# obd25k80.net
KiCad netlist of a schematic drawn in EAGLE
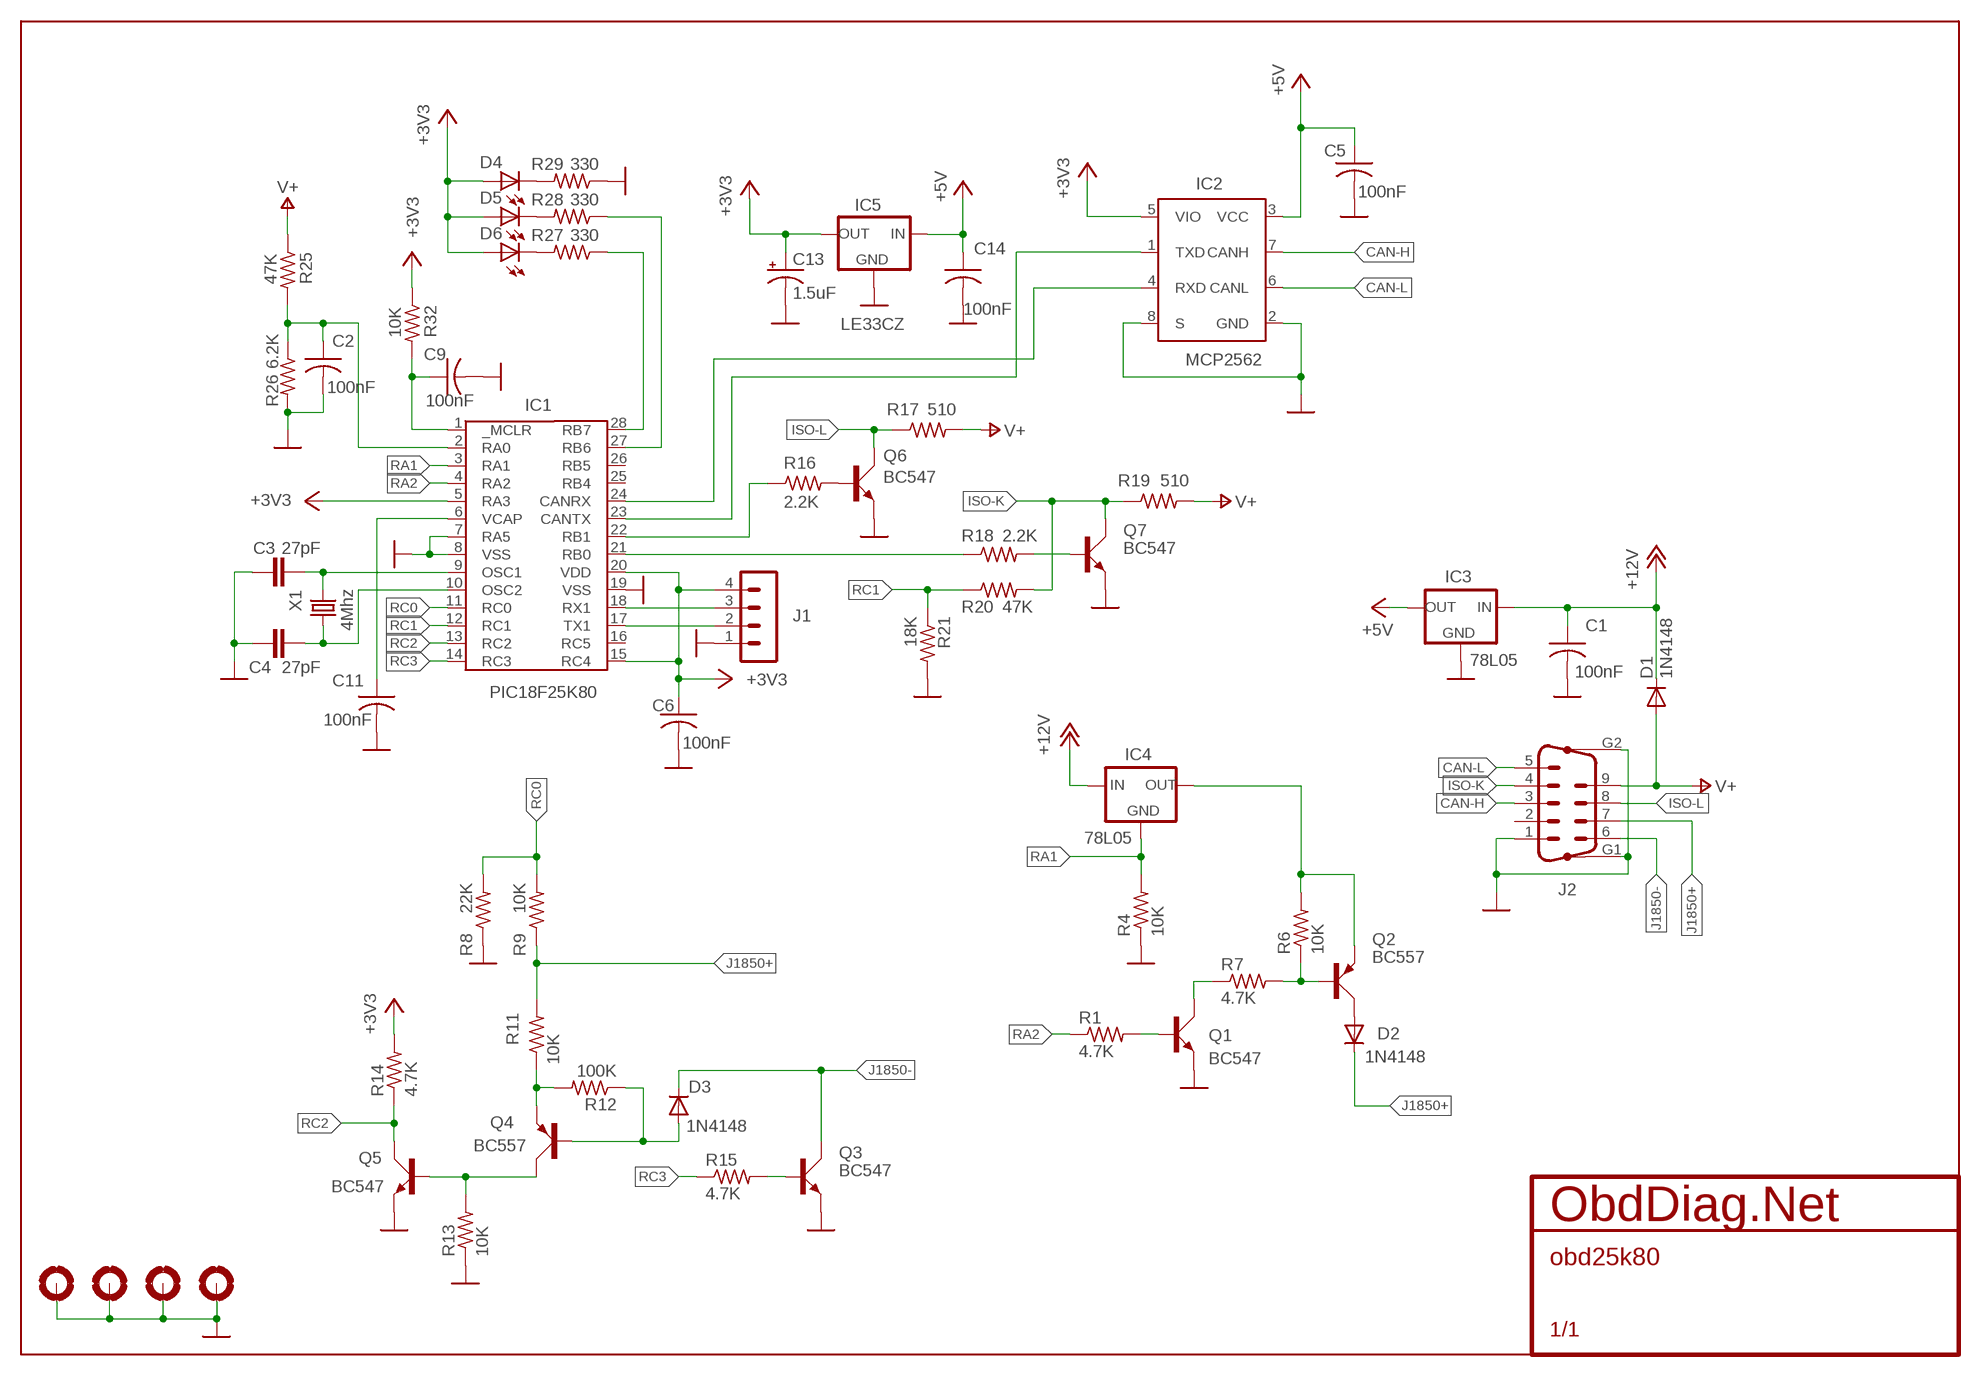
[diagram p0: schematic, sheet 1]

(export (version "E")
  (design (tool "Eeschema 10.0.6"))
  (components
    (comp (ref "C1")
      (value "100nF")
      (footprint "eagle-import:C050-025X075")
      (libsource (lib "eagle-import") (part "C-US050-025X075"))
    )
    (comp (ref "C2")
      (value "100nF")
      (footprint "eagle-import:C050-025X075")
      (libsource (lib "eagle-import") (part "C-US050-025X075"))
    )
    (comp (ref "C3")
      (value "27pF")
      (footprint "eagle-import:C2.5-2")
      (libsource (lib "eagle-import") (part "C2.5/2"))
    )
    (comp (ref "C4")
      (value "27pF")
      (footprint "eagle-import:C2.5-2")
      (libsource (lib "eagle-import") (part "C2.5/2"))
    )
    (comp (ref "C5")
      (value "100nF")
      (footprint "eagle-import:C050-025X075")
      (libsource (lib "eagle-import") (part "C-US050-025X075"))
    )
    (comp (ref "C6")
      (value "100nF")
      (footprint "eagle-import:C050-025X075")
      (libsource (lib "eagle-import") (part "C-US050-025X075"))
    )
    (comp (ref "C9")
      (value "100nF")
      (footprint "eagle-import:C050-025X075")
      (libsource (lib "eagle-import") (part "C-US050-025X075"))
    )
    (comp (ref "C11")
      (value "100nF")
      (footprint "eagle-import:C050-025X075")
      (libsource (lib "eagle-import") (part "C-US050-025X075"))
    )
    (comp (ref "C13")
      (value "1.5uF")
      (footprint "eagle-import:E2,5-5")
      (libsource (lib "eagle-import") (part "CPOL-USE2.5-5"))
    )
    (comp (ref "C14")
      (value "100nF")
      (footprint "eagle-import:C050-025X075")
      (libsource (lib "eagle-import") (part "C-US050-025X075"))
    )
    (comp (ref "D1")
      (value "1N4148")
      (footprint "eagle-import:D035-10M")
      (libsource (lib "eagle-import") (part "1N4148M"))
    )
    (comp (ref "D2")
      (value "1N4148")
      (footprint "eagle-import:D035-10M")
      (libsource (lib "eagle-import") (part "1N4148M"))
    )
    (comp (ref "D3")
      (value "1N4148")
      (footprint "eagle-import:D035-10M")
      (libsource (lib "eagle-import") (part "1N4148M"))
    )
    (comp (ref "D4")
      (value "LED5MM")
      (footprint "eagle-import:LED5MM")
      (libsource (lib "eagle-import") (part "LED5MM"))
    )
    (comp (ref "D5")
      (value "LED5MM")
      (footprint "eagle-import:LED5MM")
      (libsource (lib "eagle-import") (part "LED5MM"))
    )
    (comp (ref "D6")
      (value "LED5MM")
      (footprint "eagle-import:LED5MM")
      (libsource (lib "eagle-import") (part "LED5MM"))
    )
    (comp (ref "H1")
      (value "MOUNT-PAD-ROUND2.8")
      (footprint "eagle-import:2,8-PAD")
      (libsource (lib "eagle-import") (part "MOUNT-PAD-ROUND2.8"))
    )
    (comp (ref "H2")
      (value "MOUNT-PAD-ROUND2.8")
      (footprint "eagle-import:2,8-PAD")
      (libsource (lib "eagle-import") (part "MOUNT-PAD-ROUND2.8"))
    )
    (comp (ref "H3")
      (value "MOUNT-PAD-ROUND2.8")
      (footprint "eagle-import:2,8-PAD")
      (libsource (lib "eagle-import") (part "MOUNT-PAD-ROUND2.8"))
    )
    (comp (ref "H4")
      (value "MOUNT-PAD-ROUND2.8")
      (footprint "eagle-import:2,8-PAD")
      (libsource (lib "eagle-import") (part "MOUNT-PAD-ROUND2.8"))
    )
    (comp (ref "IC1")
      (value "PIC18F25K80")
      (footprint "eagle-import:DIL28")
      (libsource (lib "eagle-import") (part "PIC18F25K80"))
    )
    (comp (ref "IC2")
      (value "MCP2562")
      (footprint "eagle-import:DIL8")
      (libsource (lib "eagle-import") (part "MCP2562"))
    )
    (comp (ref "IC3")
      (value "78L05")
      (footprint "eagle-import:78LXX")
      (libsource (lib "eagle-import") (part "78LXX"))
    )
    (comp (ref "IC4")
      (value "78L05")
      (footprint "eagle-import:78LXX")
      (libsource (lib "eagle-import") (part "78LXX"))
    )
    (comp (ref "IC5")
      (value "LE33CZ")
      (footprint "eagle-import:78LXX")
      (libsource (lib "eagle-import") (part "78LXX"))
    )
    (comp (ref "J1")
      (value "MA04-1")
      (footprint "eagle-import:MA04-1")
      (libsource (lib "eagle-import") (part "MA04-1"))
    )
    (comp (ref "J2")
      (value "DB9-M")
      (footprint "eagle-import:M09HP")
      (libsource (lib "eagle-import") (part "M09HP"))
    )
    (comp (ref "Q1")
      (value "BC547")
      (footprint "eagle-import:SOT54A")
      (libsource (lib "eagle-import") (part "BC547"))
    )
    (comp (ref "Q2")
      (value "BC557")
      (footprint "eagle-import:SOT54A")
      (libsource (lib "eagle-import") (part "BC557"))
    )
    (comp (ref "Q3")
      (value "BC547")
      (footprint "eagle-import:SOT54A")
      (libsource (lib "eagle-import") (part "BC547"))
    )
    (comp (ref "Q4")
      (value "BC557")
      (footprint "eagle-import:SOT54A")
      (libsource (lib "eagle-import") (part "BC557"))
    )
    (comp (ref "Q5")
      (value "BC547")
      (footprint "eagle-import:SOT54A")
      (libsource (lib "eagle-import") (part "BC547"))
    )
    (comp (ref "Q6")
      (value "BC547")
      (footprint "eagle-import:SOT54A")
      (libsource (lib "eagle-import") (part "BC547"))
    )
    (comp (ref "Q7")
      (value "BC547")
      (footprint "eagle-import:SOT54A")
      (libsource (lib "eagle-import") (part "BC547"))
    )
    (comp (ref "R1")
      (value "4.7K")
      (footprint "eagle-import:0207_10")
      (libsource (lib "eagle-import") (part "R-US_0207/10"))
    )
    (comp (ref "R4")
      (value "10K")
      (footprint "eagle-import:0207_10")
      (libsource (lib "eagle-import") (part "R-US_0207/10"))
    )
    (comp (ref "R6")
      (value "10K")
      (footprint "eagle-import:0207_10")
      (libsource (lib "eagle-import") (part "R-US_0207/10"))
    )
    (comp (ref "R7")
      (value "4.7K")
      (footprint "eagle-import:0207_10")
      (libsource (lib "eagle-import") (part "R-US_0207/10"))
    )
    (comp (ref "R8")
      (value "22K")
      (footprint "eagle-import:0207_10")
      (libsource (lib "eagle-import") (part "R-US_0207/10"))
    )
    (comp (ref "R9")
      (value "10K")
      (footprint "eagle-import:0207_10")
      (libsource (lib "eagle-import") (part "R-US_0207/10"))
    )
    (comp (ref "R11")
      (value "10K")
      (footprint "eagle-import:0207_10")
      (libsource (lib "eagle-import") (part "R-US_0207/10"))
    )
    (comp (ref "R12")
      (value "100K")
      (footprint "eagle-import:0207_10")
      (libsource (lib "eagle-import") (part "R-US_0207/10"))
    )
    (comp (ref "R13")
      (value "10K")
      (footprint "eagle-import:0207_10")
      (libsource (lib "eagle-import") (part "R-US_0207/10"))
    )
    (comp (ref "R14")
      (value "4.7K")
      (footprint "eagle-import:0207_10")
      (libsource (lib "eagle-import") (part "R-US_0207/10"))
    )
    (comp (ref "R15")
      (value "4.7K")
      (footprint "eagle-import:0207_10")
      (libsource (lib "eagle-import") (part "R-US_0207/10"))
    )
    (comp (ref "R16")
      (value "2.2K")
      (footprint "eagle-import:0207_10")
      (libsource (lib "eagle-import") (part "R-US_0207/10"))
    )
    (comp (ref "R17")
      (value "510")
      (footprint "eagle-import:0207_10")
      (libsource (lib "eagle-import") (part "R-US_0207/10"))
    )
    (comp (ref "R18")
      (value "2.2K")
      (footprint "eagle-import:0207_10")
      (libsource (lib "eagle-import") (part "R-US_0207/10"))
    )
    (comp (ref "R19")
      (value "510")
      (footprint "eagle-import:0207_10")
      (libsource (lib "eagle-import") (part "R-US_0207/10"))
    )
    (comp (ref "R20")
      (value "47K")
      (footprint "eagle-import:0207_10")
      (libsource (lib "eagle-import") (part "R-US_0207/10"))
    )
    (comp (ref "R21")
      (value "18K")
      (footprint "eagle-import:0207_10")
      (libsource (lib "eagle-import") (part "R-US_0207/10"))
    )
    (comp (ref "R25")
      (value "47K")
      (footprint "eagle-import:0207_10")
      (libsource (lib "eagle-import") (part "R-US_0207/10"))
    )
    (comp (ref "R26")
      (value "6.2K")
      (footprint "eagle-import:0207_10")
      (libsource (lib "eagle-import") (part "R-US_0207/10"))
    )
    (comp (ref "R27")
      (value "330")
      (footprint "eagle-import:0207_10")
      (libsource (lib "eagle-import") (part "R-US_0207/10"))
    )
    (comp (ref "R28")
      (value "330")
      (footprint "eagle-import:0207_10")
      (libsource (lib "eagle-import") (part "R-US_0207/10"))
    )
    (comp (ref "R29")
      (value "330")
      (footprint "eagle-import:0207_10")
      (libsource (lib "eagle-import") (part "R-US_0207/10"))
    )
    (comp (ref "R32")
      (value "10K")
      (footprint "eagle-import:0207_10")
      (libsource (lib "eagle-import") (part "R-US_0207/10"))
    )
    (comp (ref "X1")
      (value "4Mhz")
      (footprint "eagle-import:HC49_S")
      (libsource (lib "eagle-import") (part "CRYTALHC49S"))
    )
  )
  (nets
    (net (code "1") (name "+3V3") (class "Default")
      (node (ref "C13") (pin "+") (pinfunction "+_+") (pintype "passive"))
      (node (ref "C6") (pin "1") (pinfunction "1_1") (pintype "passive"))
      (node (ref "D4") (pin "A") (pinfunction "A_A") (pintype "passive"))
      (node (ref "D5") (pin "A") (pinfunction "A_A") (pintype "passive"))
      (node (ref "D6") (pin "A") (pinfunction "A_A") (pintype "passive"))
      (node (ref "IC1") (pin "15") (pinfunction "RC4_15") (pintype "bidirectional"))
      (node (ref "IC1") (pin "20") (pinfunction "VDD_20") (pintype "power_in"))
      (node (ref "IC1") (pin "5") (pinfunction "RA3_5") (pintype "bidirectional"))
      (node (ref "IC2") (pin "5") (pinfunction "VIO_5") (pintype "power_in"))
      (node (ref "IC5") (pin "OUT") (pinfunction "OUT_OUT") (pintype "passive"))
      (node (ref "J1") (pin "4") (pinfunction "4_4") (pintype "passive"))
      (node (ref "R14") (pin "2") (pinfunction "2_2") (pintype "passive"))
      (node (ref "R32") (pin "1") (pinfunction "1_1") (pintype "passive"))
    )
    (net (code "2") (name "+5V") (class "Default")
      (node (ref "C14") (pin "1") (pinfunction "1_1") (pintype "passive"))
      (node (ref "C5") (pin "1") (pinfunction "1_1") (pintype "passive"))
      (node (ref "IC2") (pin "3") (pinfunction "VCC_3") (pintype "power_in"))
      (node (ref "IC3") (pin "OUT") (pinfunction "OUT_OUT") (pintype "passive"))
      (node (ref "IC5") (pin "IN") (pinfunction "IN_IN") (pintype "input"))
    )
    (net (code "3") (name "+12V") (class "Default")
      (node (ref "C1") (pin "1") (pinfunction "1_1") (pintype "passive"))
      (node (ref "D1") (pin "C") (pinfunction "C_C") (pintype "passive"))
      (node (ref "IC3") (pin "IN") (pinfunction "IN_IN") (pintype "input"))
      (node (ref "IC4") (pin "IN") (pinfunction "IN_IN") (pintype "input"))
    )
    (net (code "4") (name "CAN-H") (class "Default")
      (node (ref "IC2") (pin "7") (pinfunction "CANH_7") (pintype "bidirectional"))
      (node (ref "J2") (pin "3") (pinfunction "3_3") (pintype "passive"))
    )
    (net (code "5") (name "CAN-L") (class "Default")
      (node (ref "IC2") (pin "6") (pinfunction "CANL_6") (pintype "bidirectional"))
      (node (ref "J2") (pin "5") (pinfunction "5_5") (pintype "passive"))
    )
    (net (code "6") (name "GND") (class "Default")
      (node (ref "C1") (pin "2") (pinfunction "2_2") (pintype "passive"))
      (node (ref "C11") (pin "2") (pinfunction "2_2") (pintype "passive"))
      (node (ref "C13") (pin "-") (pinfunction "-_-") (pintype "passive"))
      (node (ref "C14") (pin "2") (pinfunction "2_2") (pintype "passive"))
      (node (ref "C2") (pin "2") (pinfunction "2_2") (pintype "passive"))
      (node (ref "C3") (pin "1") (pinfunction "1_1") (pintype "passive"))
      (node (ref "C4") (pin "2") (pinfunction "2_2") (pintype "passive"))
      (node (ref "C5") (pin "2") (pinfunction "2_2") (pintype "passive"))
      (node (ref "C6") (pin "2") (pinfunction "2_2") (pintype "passive"))
      (node (ref "C9") (pin "2") (pinfunction "2_2") (pintype "passive"))
      (node (ref "H1") (pin "B2,8") (pinfunction "MOUNT_B2,8") (pintype "passive"))
      (node (ref "H2") (pin "B2,8") (pinfunction "MOUNT_B2,8") (pintype "passive"))
      (node (ref "H3") (pin "B2,8") (pinfunction "MOUNT_B2,8") (pintype "passive"))
      (node (ref "H4") (pin "B2,8") (pinfunction "MOUNT_B2,8") (pintype "passive"))
      (node (ref "IC1") (pin "19") (pinfunction "VSS_19") (pintype "power_in"))
      (node (ref "IC1") (pin "7") (pinfunction "RA5_7") (pintype "bidirectional"))
      (node (ref "IC1") (pin "8") (pinfunction "VSS_8") (pintype "power_in"))
      (node (ref "IC2") (pin "2") (pinfunction "GND_2") (pintype "power_in"))
      (node (ref "IC2") (pin "8") (pinfunction "S_8") (pintype "input"))
      (node (ref "IC3") (pin "GND") (pinfunction "GND_GND") (pintype "input"))
      (node (ref "IC5") (pin "GND") (pinfunction "GND_GND") (pintype "input"))
      (node (ref "J1") (pin "1") (pinfunction "1_1") (pintype "passive"))
      (node (ref "J2") (pin "1") (pinfunction "1_1") (pintype "passive"))
      (node (ref "J2") (pin "G1") (pinfunction "G1_G1") (pintype "passive"))
      (node (ref "J2") (pin "G2") (pinfunction "G2_G2") (pintype "passive"))
      (node (ref "Q1") (pin "E") (pinfunction "E_E") (pintype "passive"))
      (node (ref "Q3") (pin "E") (pinfunction "E_E") (pintype "passive"))
      (node (ref "Q5") (pin "E") (pinfunction "E_E") (pintype "passive"))
      (node (ref "Q6") (pin "E") (pinfunction "E_E") (pintype "passive"))
      (node (ref "Q7") (pin "E") (pinfunction "E_E") (pintype "passive"))
      (node (ref "R13") (pin "1") (pinfunction "1_1") (pintype "passive"))
      (node (ref "R21") (pin "2") (pinfunction "2_2") (pintype "passive"))
      (node (ref "R26") (pin "2") (pinfunction "2_2") (pintype "passive"))
      (node (ref "R29") (pin "1") (pinfunction "1_1") (pintype "passive"))
      (node (ref "R4") (pin "1") (pinfunction "1_1") (pintype "passive"))
      (node (ref "R8") (pin "1") (pinfunction "1_1") (pintype "passive"))
    )
    (net (code "7") (name "ISO-K") (class "Default")
      (node (ref "J2") (pin "4") (pinfunction "4_4") (pintype "passive"))
      (node (ref "Q7") (pin "C") (pinfunction "C_C") (pintype "passive"))
      (node (ref "R19") (pin "1") (pinfunction "1_1") (pintype "passive"))
      (node (ref "R20") (pin "2") (pinfunction "2_2") (pintype "passive"))
    )
    (net (code "8") (name "ISO-L") (class "Default")
      (node (ref "J2") (pin "8") (pinfunction "8_8") (pintype "passive"))
      (node (ref "Q6") (pin "C") (pinfunction "C_C") (pintype "passive"))
      (node (ref "R17") (pin "1") (pinfunction "1_1") (pintype "passive"))
    )
    (net (code "9") (name "J1850+") (class "Default")
      (node (ref "D2") (pin "C") (pinfunction "C_C") (pintype "passive"))
      (node (ref "J2") (pin "7") (pinfunction "7_7") (pintype "passive"))
      (node (ref "R11") (pin "2") (pinfunction "2_2") (pintype "passive"))
      (node (ref "R9") (pin "1") (pinfunction "1_1") (pintype "passive"))
    )
    (net (code "10") (name "J1850-") (class "Default")
      (node (ref "D3") (pin "C") (pinfunction "C_C") (pintype "passive"))
      (node (ref "J2") (pin "6") (pinfunction "6_6") (pintype "passive"))
      (node (ref "Q3") (pin "C") (pinfunction "C_C") (pintype "passive"))
    )
    (net (code "11") (name "Net-(D2-PadA)") (class "Default")
      (node (ref "D2") (pin "A") (pinfunction "A_A") (pintype "passive"))
      (node (ref "Q2") (pin "C") (pinfunction "C_C") (pintype "passive"))
    )
    (net (code "12") (name "Net-(D3-PadA)") (class "Default")
      (node (ref "D3") (pin "A") (pinfunction "A_A") (pintype "passive"))
      (node (ref "Q4") (pin "B") (pinfunction "B_B") (pintype "passive"))
      (node (ref "R12") (pin "1") (pinfunction "1_1") (pintype "passive"))
    )
    (net (code "13") (name "Net-(D4-C)") (class "Default")
      (node (ref "D4") (pin "K") (pinfunction "C_K") (pintype "passive"))
      (node (ref "R29") (pin "2") (pinfunction "2_2") (pintype "passive"))
    )
    (net (code "14") (name "Net-(D5-C)") (class "Default")
      (node (ref "D5") (pin "K") (pinfunction "C_K") (pintype "passive"))
      (node (ref "R28") (pin "2") (pinfunction "2_2") (pintype "passive"))
    )
    (net (code "15") (name "Net-(D6-C)") (class "Default")
      (node (ref "D6") (pin "K") (pinfunction "C_K") (pintype "passive"))
      (node (ref "R27") (pin "2") (pinfunction "2_2") (pintype "passive"))
    )
    (net (code "16") (name "Net-(IC1-CANRX)") (class "Default")
      (node (ref "IC1") (pin "24") (pinfunction "CANRX_24") (pintype "bidirectional"))
      (node (ref "IC2") (pin "4") (pinfunction "RXD_4") (pintype "output"))
    )
    (net (code "17") (name "Net-(IC1-CANTX)") (class "Default")
      (node (ref "IC1") (pin "23") (pinfunction "CANTX_23") (pintype "bidirectional"))
      (node (ref "IC2") (pin "1") (pinfunction "TXD_1") (pintype "input"))
    )
    (net (code "18") (name "Net-(IC1-OSC1)") (class "Default")
      (node (ref "C3") (pin "2") (pinfunction "2_2") (pintype "passive"))
      (node (ref "IC1") (pin "9") (pinfunction "OSC1_9") (pintype "bidirectional"))
      (node (ref "X1") (pin "2") (pinfunction "2_2") (pintype "passive"))
    )
    (net (code "19") (name "Net-(IC1-OSC2)") (class "Default")
      (node (ref "C4") (pin "1") (pinfunction "1_1") (pintype "passive"))
      (node (ref "IC1") (pin "10") (pinfunction "OSC2_10") (pintype "bidirectional"))
      (node (ref "X1") (pin "1") (pinfunction "1_1") (pintype "passive"))
    )
    (net (code "20") (name "Net-(IC1-RA0)") (class "Default")
      (node (ref "C2") (pin "1") (pinfunction "1_1") (pintype "passive"))
      (node (ref "IC1") (pin "2") (pinfunction "RA0_2") (pintype "bidirectional"))
      (node (ref "R25") (pin "2") (pinfunction "2_2") (pintype "passive"))
      (node (ref "R26") (pin "1") (pinfunction "1_1") (pintype "passive"))
    )
    (net (code "21") (name "Net-(IC1-RB0)") (class "Default")
      (node (ref "IC1") (pin "21") (pinfunction "RB0_21") (pintype "bidirectional"))
      (node (ref "R18") (pin "1") (pinfunction "1_1") (pintype "passive"))
    )
    (net (code "22") (name "Net-(IC1-RB1)") (class "Default")
      (node (ref "IC1") (pin "22") (pinfunction "RB1_22") (pintype "bidirectional"))
      (node (ref "R16") (pin "1") (pinfunction "1_1") (pintype "passive"))
    )
    (net (code "23") (name "Net-(IC1-RB6)") (class "Default")
      (node (ref "IC1") (pin "27") (pinfunction "RB6_27") (pintype "bidirectional"))
      (node (ref "R28") (pin "1") (pinfunction "1_1") (pintype "passive"))
    )
    (net (code "24") (name "Net-(IC1-RB7)") (class "Default")
      (node (ref "IC1") (pin "28") (pinfunction "RB7_28") (pintype "bidirectional"))
      (node (ref "R27") (pin "1") (pinfunction "1_1") (pintype "passive"))
    )
    (net (code "25") (name "Net-(IC1-RX1)") (class "Default")
      (node (ref "IC1") (pin "18") (pinfunction "RX1_18") (pintype "bidirectional"))
      (node (ref "J1") (pin "3") (pinfunction "3_3") (pintype "passive"))
    )
    (net (code "26") (name "Net-(IC1-TX1)") (class "Default")
      (node (ref "IC1") (pin "17") (pinfunction "TX1_17") (pintype "bidirectional"))
      (node (ref "J1") (pin "2") (pinfunction "2_2") (pintype "passive"))
    )
    (net (code "27") (name "Net-(IC1-VCAP)") (class "Default")
      (node (ref "C11") (pin "1") (pinfunction "1_1") (pintype "passive"))
      (node (ref "IC1") (pin "6") (pinfunction "VCAP_6") (pintype "passive"))
    )
    (net (code "28") (name "Net-(IC1-_MCLR)") (class "Default")
      (node (ref "C9") (pin "1") (pinfunction "1_1") (pintype "passive"))
      (node (ref "IC1") (pin "1") (pinfunction "_MCLR_1") (pintype "bidirectional"))
      (node (ref "R32") (pin "2") (pinfunction "2_2") (pintype "passive"))
    )
    (net (code "29") (name "Net-(IC4-PadOUT)") (class "Default")
      (node (ref "IC4") (pin "OUT") (pinfunction "OUT_OUT") (pintype "passive"))
      (node (ref "Q2") (pin "E") (pinfunction "E_E") (pintype "passive"))
      (node (ref "R6") (pin "2") (pinfunction "2_2") (pintype "passive"))
    )
    (net (code "30") (name "Net-(Q1-PadB)") (class "Default")
      (node (ref "Q1") (pin "B") (pinfunction "B_B") (pintype "passive"))
      (node (ref "R1") (pin "2") (pinfunction "2_2") (pintype "passive"))
    )
    (net (code "31") (name "Net-(Q1-PadC)") (class "Default")
      (node (ref "Q1") (pin "C") (pinfunction "C_C") (pintype "passive"))
      (node (ref "R7") (pin "1") (pinfunction "1_1") (pintype "passive"))
    )
    (net (code "32") (name "Net-(Q2-PadB)") (class "Default")
      (node (ref "Q2") (pin "B") (pinfunction "B_B") (pintype "passive"))
      (node (ref "R6") (pin "1") (pinfunction "1_1") (pintype "passive"))
      (node (ref "R7") (pin "2") (pinfunction "2_2") (pintype "passive"))
    )
    (net (code "33") (name "Net-(Q3-PadB)") (class "Default")
      (node (ref "Q3") (pin "B") (pinfunction "B_B") (pintype "passive"))
      (node (ref "R15") (pin "2") (pinfunction "2_2") (pintype "passive"))
    )
    (net (code "34") (name "Net-(Q4-PadC)") (class "Default")
      (node (ref "Q4") (pin "C") (pinfunction "C_C") (pintype "passive"))
      (node (ref "Q5") (pin "B") (pinfunction "B_B") (pintype "passive"))
      (node (ref "R13") (pin "2") (pinfunction "2_2") (pintype "passive"))
    )
    (net (code "35") (name "Net-(Q4-PadE)") (class "Default")
      (node (ref "Q4") (pin "E") (pinfunction "E_E") (pintype "passive"))
      (node (ref "R11") (pin "1") (pinfunction "1_1") (pintype "passive"))
      (node (ref "R12") (pin "2") (pinfunction "2_2") (pintype "passive"))
    )
    (net (code "36") (name "Net-(Q6-PadB)") (class "Default")
      (node (ref "Q6") (pin "B") (pinfunction "B_B") (pintype "passive"))
      (node (ref "R16") (pin "2") (pinfunction "2_2") (pintype "passive"))
    )
    (net (code "37") (name "Net-(Q7-PadB)") (class "Default")
      (node (ref "Q7") (pin "B") (pinfunction "B_B") (pintype "passive"))
      (node (ref "R18") (pin "2") (pinfunction "2_2") (pintype "passive"))
    )
    (net (code "38") (name "RA1") (class "Default")
      (node (ref "IC1") (pin "3") (pinfunction "RA1_3") (pintype "bidirectional"))
      (node (ref "IC4") (pin "GND") (pinfunction "GND_GND") (pintype "input"))
      (node (ref "R4") (pin "2") (pinfunction "2_2") (pintype "passive"))
    )
    (net (code "39") (name "RA2") (class "Default")
      (node (ref "IC1") (pin "4") (pinfunction "RA2_4") (pintype "bidirectional"))
      (node (ref "R1") (pin "1") (pinfunction "1_1") (pintype "passive"))
    )
    (net (code "40") (name "RC0") (class "Default")
      (node (ref "IC1") (pin "11") (pinfunction "RC0_11") (pintype "bidirectional"))
      (node (ref "R8") (pin "2") (pinfunction "2_2") (pintype "passive"))
      (node (ref "R9") (pin "2") (pinfunction "2_2") (pintype "passive"))
    )
    (net (code "41") (name "RC1") (class "Default")
      (node (ref "IC1") (pin "12") (pinfunction "RC1_12") (pintype "bidirectional"))
      (node (ref "R20") (pin "1") (pinfunction "1_1") (pintype "passive"))
      (node (ref "R21") (pin "1") (pinfunction "1_1") (pintype "passive"))
    )
    (net (code "42") (name "RC2") (class "Default")
      (node (ref "IC1") (pin "13") (pinfunction "RC2_13") (pintype "bidirectional"))
      (node (ref "Q5") (pin "C") (pinfunction "C_C") (pintype "passive"))
      (node (ref "R14") (pin "1") (pinfunction "1_1") (pintype "passive"))
    )
    (net (code "43") (name "RC3") (class "Default")
      (node (ref "IC1") (pin "14") (pinfunction "RC3_14") (pintype "bidirectional"))
      (node (ref "R15") (pin "1") (pinfunction "1_1") (pintype "passive"))
    )
    (net (code "44") (name "V+") (class "Default")
      (node (ref "D1") (pin "A") (pinfunction "A_A") (pintype "passive"))
      (node (ref "J2") (pin "9") (pinfunction "9_9") (pintype "passive"))
      (node (ref "R17") (pin "2") (pinfunction "2_2") (pintype "passive"))
      (node (ref "R19") (pin "2") (pinfunction "2_2") (pintype "passive"))
      (node (ref "R25") (pin "1") (pinfunction "1_1") (pintype "passive"))
    )
    (net (code "45") (name "unconnected-(IC1-RB4-Pad25)") (class "Default")
      (node (ref "IC1") (pin "25") (pinfunction "RB4_25") (pintype "bidirectional"))
    )
    (net (code "46") (name "unconnected-(IC1-RB5-Pad26)") (class "Default")
      (node (ref "IC1") (pin "26") (pinfunction "RB5_26") (pintype "bidirectional"))
    )
    (net (code "47") (name "unconnected-(IC1-RC5-Pad16)") (class "Default")
      (node (ref "IC1") (pin "16") (pinfunction "RC5_16") (pintype "bidirectional"))
    )
    (net (code "48") (name "unconnected-(J2-Pad2)") (class "Default")
      (node (ref "J2") (pin "2") (pinfunction "2_2") (pintype "passive"))
    )
  )
)
